# owc-transmitter-ir-v2.net
KiCad netlist of a schematic drawn in EAGLE
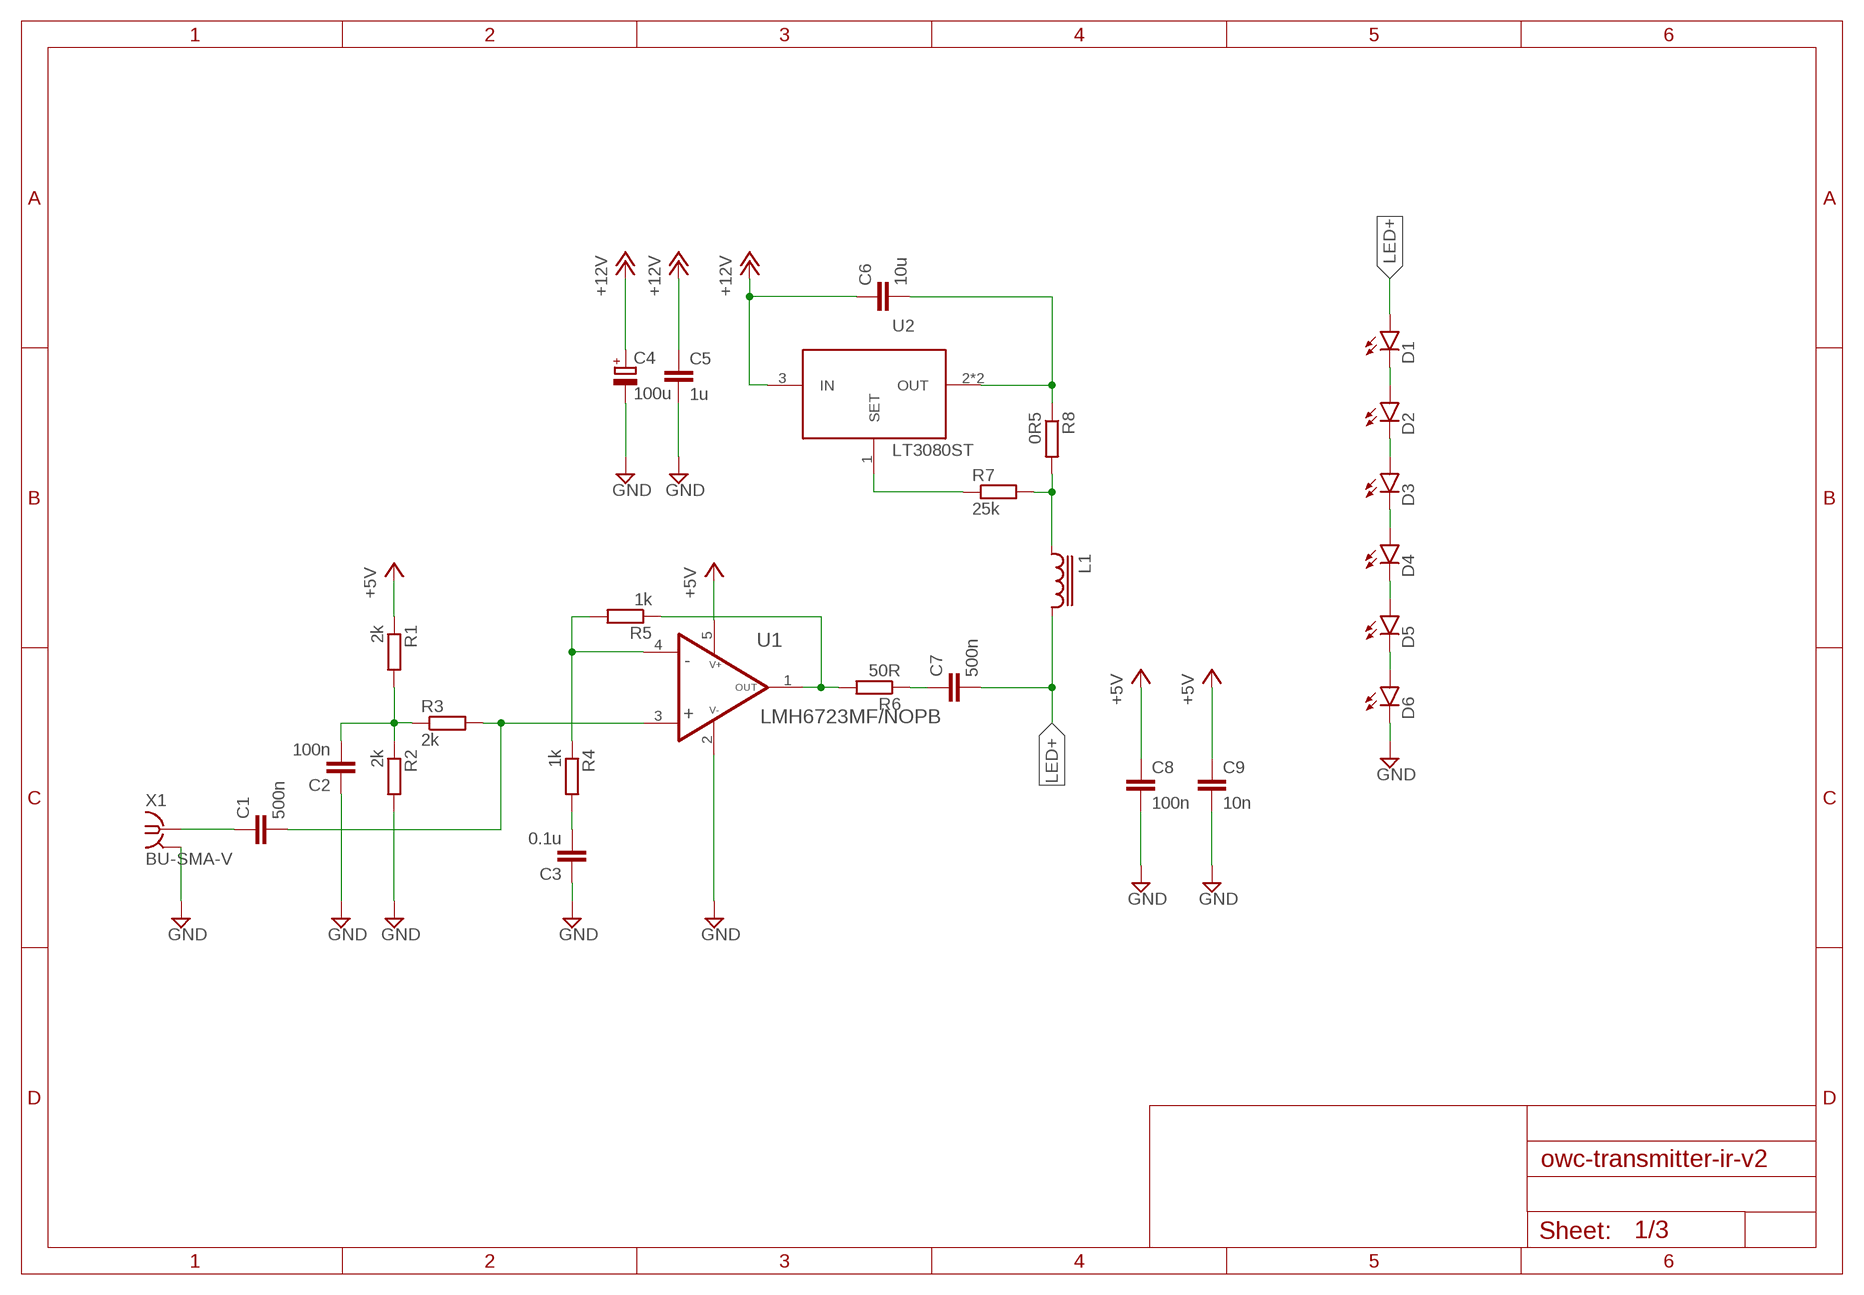
[diagram p0: schematic, sheet 1]
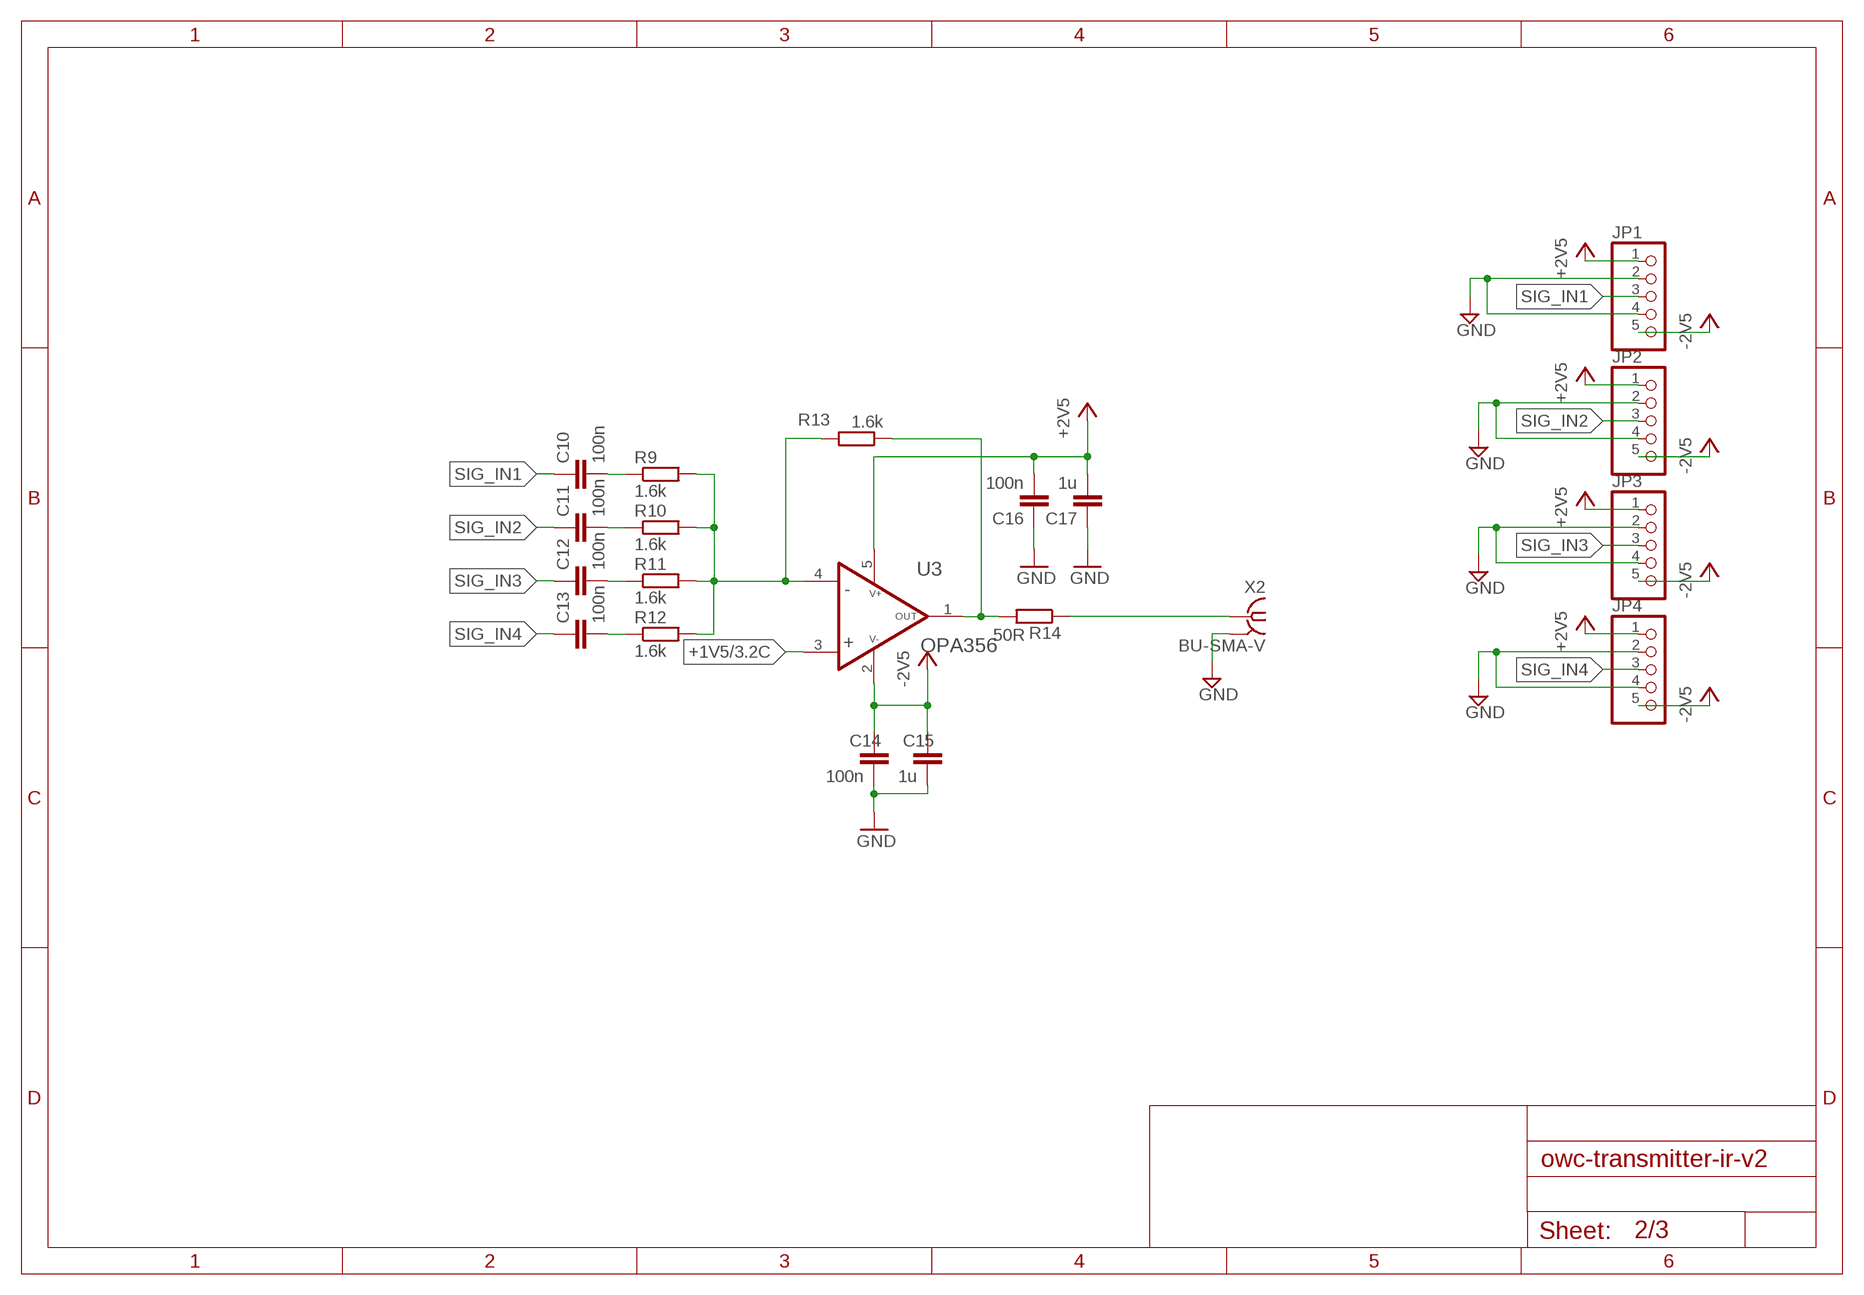
[diagram p1: schematic, sheet 2]
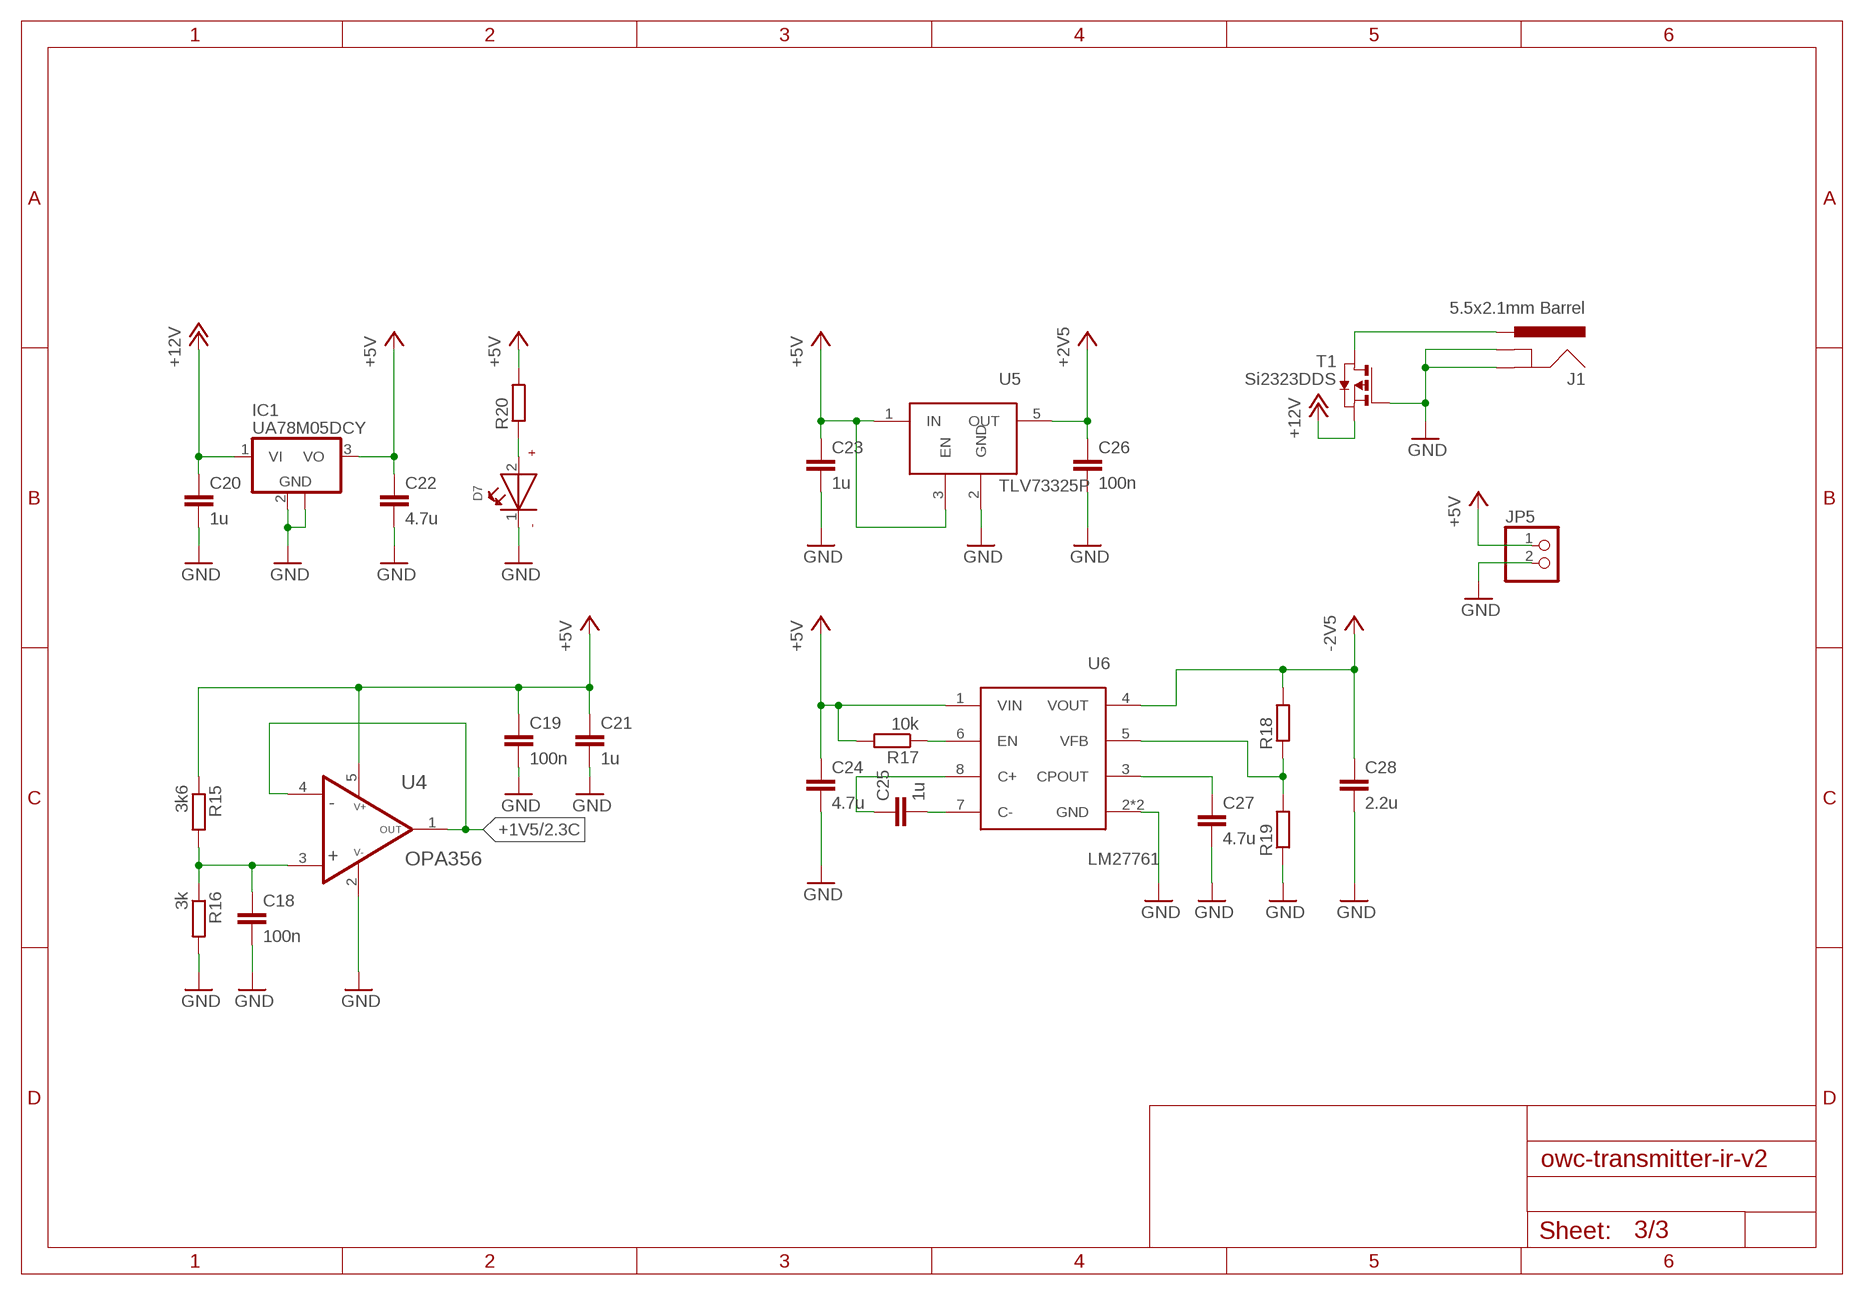
[diagram p2: schematic, sheet 3]

(export (version "E")
  (design (tool "Eeschema 10.0.6"))
  (components
    (comp (ref "C10")
      (value "100n")
      (footprint "eagle-import:C0805")
      (libsource (lib "eagle-import") (part "C-EUC0805"))
    )
    (comp (ref "C11")
      (value "100n")
      (footprint "eagle-import:C0805")
      (libsource (lib "eagle-import") (part "C-EUC0805"))
    )
    (comp (ref "C12")
      (value "100n")
      (footprint "eagle-import:C0805")
      (libsource (lib "eagle-import") (part "C-EUC0805"))
    )
    (comp (ref "C13")
      (value "100n")
      (footprint "eagle-import:C0805")
      (libsource (lib "eagle-import") (part "C-EUC0805"))
    )
    (comp (ref "C14")
      (value "100n")
      (footprint "eagle-import:C0805")
      (libsource (lib "eagle-import") (part "C-EUC0805"))
    )
    (comp (ref "C15")
      (value "1u")
      (footprint "eagle-import:C0805")
      (libsource (lib "eagle-import") (part "C-EUC0805"))
    )
    (comp (ref "C16")
      (value "100n")
      (footprint "eagle-import:C0805")
      (libsource (lib "eagle-import") (part "C-EUC0805"))
    )
    (comp (ref "C17")
      (value "1u")
      (footprint "eagle-import:C0805")
      (libsource (lib "eagle-import") (part "C-EUC0805"))
    )
    (comp (ref "JP1")
      (value "PINHD-1X5")
      (footprint "eagle-import:1X05")
      (libsource (lib "eagle-import") (part "PINHD-1X5"))
    )
    (comp (ref "JP2")
      (value "PINHD-1X5")
      (footprint "eagle-import:1X05")
      (libsource (lib "eagle-import") (part "PINHD-1X5"))
    )
    (comp (ref "JP3")
      (value "PINHD-1X5")
      (footprint "eagle-import:1X05")
      (libsource (lib "eagle-import") (part "PINHD-1X5"))
    )
    (comp (ref "JP4")
      (value "PINHD-1X5")
      (footprint "eagle-import:1X05")
      (libsource (lib "eagle-import") (part "PINHD-1X5"))
    )
    (comp (ref "R9")
      (value "1.6k")
      (footprint "eagle-import:R0805")
      (libsource (lib "eagle-import") (part "R-EU_R0805"))
    )
    (comp (ref "R10")
      (value "1.6k")
      (footprint "eagle-import:R0805")
      (libsource (lib "eagle-import") (part "R-EU_R0805"))
    )
    (comp (ref "R11")
      (value "1.6k")
      (footprint "eagle-import:R0805")
      (libsource (lib "eagle-import") (part "R-EU_R0805"))
    )
    (comp (ref "R12")
      (value "1.6k")
      (footprint "eagle-import:R0805")
      (libsource (lib "eagle-import") (part "R-EU_R0805"))
    )
    (comp (ref "R13")
      (value "1.6k")
      (footprint "eagle-import:R0805")
      (libsource (lib "eagle-import") (part "R-EU_R0805"))
    )
    (comp (ref "R14")
      (value "50R")
      (footprint "eagle-import:R0805")
      (libsource (lib "eagle-import") (part "R-EU_R0805"))
    )
    (comp (ref "U3")
      (value "OPA356")
      (footprint "eagle-import:SOT23-5L")
      (libsource (lib "eagle-import") (part "LMH6629MF"))
    )
    (comp (ref "X2")
      (value "BU-SMA-V")
      (footprint "eagle-import:BU-SMA-V")
      (libsource (lib "eagle-import") (part "BU-SMA-V"))
    )
    (comp (ref "C1")
      (value "500n")
      (footprint "eagle-import:C0805")
      (libsource (lib "eagle-import") (part "C-EUC0805"))
    )
    (comp (ref "C2")
      (value "100n")
      (footprint "eagle-import:C0805")
      (libsource (lib "eagle-import") (part "C-EUC0805"))
    )
    (comp (ref "C3")
      (value "0.1u")
      (footprint "eagle-import:C0805")
      (libsource (lib "eagle-import") (part "C-EUC0805"))
    )
    (comp (ref "C4")
      (value "100u")
      (footprint "eagle-import:CT3528")
      (libsource (lib "eagle-import") (part "CPOL-EUCT3528"))
    )
    (comp (ref "C5")
      (value "1u")
      (footprint "eagle-import:C0805")
      (libsource (lib "eagle-import") (part "C-EUC0805"))
    )
    (comp (ref "C6")
      (value "10u")
      (footprint "eagle-import:C0805")
      (libsource (lib "eagle-import") (part "C-EUC0805"))
    )
    (comp (ref "C7")
      (value "500n")
      (footprint "eagle-import:C0805")
      (libsource (lib "eagle-import") (part "C-EUC0805"))
    )
    (comp (ref "C8")
      (value "100n")
      (footprint "eagle-import:C0805")
      (libsource (lib "eagle-import") (part "C-EUC0805"))
    )
    (comp (ref "C9")
      (value "10n")
      (footprint "eagle-import:C0805")
      (libsource (lib "eagle-import") (part "C-EUC0805"))
    )
    (comp (ref "D1")
      (value "LED5MM")
      (footprint "eagle-import:LED5MM")
      (libsource (lib "eagle-import") (part "LED5MM"))
    )
    (comp (ref "D2")
      (value "LED5MM")
      (footprint "eagle-import:LED5MM")
      (libsource (lib "eagle-import") (part "LED5MM"))
    )
    (comp (ref "D3")
      (value "LED5MM")
      (footprint "eagle-import:LED5MM")
      (libsource (lib "eagle-import") (part "LED5MM"))
    )
    (comp (ref "D4")
      (value "LED5MM")
      (footprint "eagle-import:LED5MM")
      (libsource (lib "eagle-import") (part "LED5MM"))
    )
    (comp (ref "D5")
      (value "LED5MM")
      (footprint "eagle-import:LED5MM")
      (libsource (lib "eagle-import") (part "LED5MM"))
    )
    (comp (ref "D6")
      (value "LED5MM")
      (footprint "eagle-import:LED5MM")
      (libsource (lib "eagle-import") (part "LED5MM"))
    )
    (comp (ref "L1")
      (value "SRR6603")
      (footprint "eagle-import:SRR6603")
      (libsource (lib "eagle-import") (part "SRR6603"))
    )
    (comp (ref "R1")
      (value "2k")
      (footprint "eagle-import:R0805")
      (libsource (lib "eagle-import") (part "R-EU_R0805"))
    )
    (comp (ref "R2")
      (value "2k")
      (footprint "eagle-import:R0805")
      (libsource (lib "eagle-import") (part "R-EU_R0805"))
    )
    (comp (ref "R3")
      (value "2k")
      (footprint "eagle-import:R0805")
      (libsource (lib "eagle-import") (part "R-EU_R0805"))
    )
    (comp (ref "R4")
      (value "1k")
      (footprint "eagle-import:R0805")
      (libsource (lib "eagle-import") (part "R-EU_R0805"))
    )
    (comp (ref "R5")
      (value "1k")
      (footprint "eagle-import:R0805")
      (libsource (lib "eagle-import") (part "R-EU_R0805"))
    )
    (comp (ref "R6")
      (value "50R")
      (footprint "eagle-import:R0805")
      (libsource (lib "eagle-import") (part "R-EU_R0805"))
    )
    (comp (ref "R7")
      (value "25k")
      (footprint "eagle-import:R0805")
      (libsource (lib "eagle-import") (part "R-EU_R0805"))
    )
    (comp (ref "R8")
      (value "0R5")
      (footprint "eagle-import:R0805")
      (libsource (lib "eagle-import") (part "R-EU_R0805"))
    )
    (comp (ref "U1")
      (value "LMH6723MF/NOPB")
      (footprint "eagle-import:SOT23-5L")
      (libsource (lib "eagle-import") (part "LMH6723MF/NOPB"))
    )
    (comp (ref "U2")
      (value "LT3080ST")
      (footprint "eagle-import:SOT223")
      (libsource (lib "eagle-import") (part "LT3080ST"))
    )
    (comp (ref "X1")
      (value "BU-SMA-V")
      (footprint "eagle-import:BU-SMA-V")
      (libsource (lib "eagle-import") (part "BU-SMA-V"))
    )
    (comp (ref "C18")
      (value "100n")
      (footprint "eagle-import:C0805")
      (libsource (lib "eagle-import") (part "C-EUC0805"))
    )
    (comp (ref "C19")
      (value "100n")
      (footprint "eagle-import:C0805")
      (libsource (lib "eagle-import") (part "C-EUC0805"))
    )
    (comp (ref "C20")
      (value "1u")
      (footprint "eagle-import:C0805")
      (libsource (lib "eagle-import") (part "C-EUC0805"))
    )
    (comp (ref "C21")
      (value "1u")
      (footprint "eagle-import:C0805")
      (libsource (lib "eagle-import") (part "C-EUC0805"))
    )
    (comp (ref "C22")
      (value "4.7u")
      (footprint "eagle-import:C0805")
      (libsource (lib "eagle-import") (part "C-EUC0805"))
    )
    (comp (ref "C23")
      (value "1u")
      (footprint "eagle-import:C0805")
      (libsource (lib "eagle-import") (part "C-EUC0805"))
    )
    (comp (ref "C24")
      (value "4.7u")
      (footprint "eagle-import:C0805")
      (libsource (lib "eagle-import") (part "C-EUC0805"))
    )
    (comp (ref "C25")
      (value "1u")
      (footprint "eagle-import:C0805")
      (libsource (lib "eagle-import") (part "C-EUC0805"))
    )
    (comp (ref "C26")
      (value "100n")
      (footprint "eagle-import:C0805")
      (libsource (lib "eagle-import") (part "C-EUC0805"))
    )
    (comp (ref "C27")
      (value "4.7u")
      (footprint "eagle-import:C0805")
      (libsource (lib "eagle-import") (part "C-EUC0805"))
    )
    (comp (ref "C28")
      (value "2.2u")
      (footprint "eagle-import:C0805")
      (libsource (lib "eagle-import") (part "C-EUC0805"))
    )
    (comp (ref "D7")
      (value "WL-SMCW-150080GS75000-G")
      (footprint "eagle-import:WL-SMCW_0805")
      (libsource (lib "eagle-import") (part "WL-SMCW-150080GS75000-G"))
    )
    (comp (ref "IC1")
      (value "UA78M05DCY")
      (footprint "eagle-import:SOT223")
      (libsource (lib "eagle-import") (part "UA78MDCY05"))
    )
    (comp (ref "J1")
      (value "5.5x2.1mm Barrel")
      (footprint "eagle-import:POWER_JACK_SMD")
      (libsource (lib "eagle-import") (part "POWER_JACKSMD"))
    )
    (comp (ref "JP5")
      (value "PINHD-1X2")
      (footprint "eagle-import:1X02")
      (libsource (lib "eagle-import") (part "PINHD-1X2"))
    )
    (comp (ref "R15")
      (value "3k6")
      (footprint "eagle-import:R0805")
      (libsource (lib "eagle-import") (part "R-EU_R0805"))
    )
    (comp (ref "R16")
      (value "3k")
      (footprint "eagle-import:R0805")
      (libsource (lib "eagle-import") (part "R-EU_R0805"))
    )
    (comp (ref "R17")
      (value "10k")
      (footprint "eagle-import:R0805")
      (libsource (lib "eagle-import") (part "R-EU_R0805"))
    )
    (comp (ref "R18")
      (value "R-EU_R0805")
      (footprint "eagle-import:R0805")
      (libsource (lib "eagle-import") (part "R-EU_R0805"))
    )
    (comp (ref "R19")
      (value "R-EU_R0805")
      (footprint "eagle-import:R0805")
      (libsource (lib "eagle-import") (part "R-EU_R0805"))
    )
    (comp (ref "R20")
      (value "R-EU_R0805")
      (footprint "eagle-import:R0805")
      (libsource (lib "eagle-import") (part "R-EU_R0805"))
    )
    (comp (ref "T1")
      (value "Si2323DDS")
      (footprint "eagle-import:SOT-23")
      (libsource (lib "eagle-import") (part "PMOSSOT23"))
    )
    (comp (ref "U4")
      (value "OPA356")
      (footprint "eagle-import:SOT23-5L")
      (libsource (lib "eagle-import") (part "LMH6629MF"))
    )
    (comp (ref "U5")
      (value "TLV73325P")
      (footprint "eagle-import:SOT23-5L")
      (libsource (lib "eagle-import") (part "V_REG5-FIXEDEN"))
    )
    (comp (ref "U6")
      (value "LM27761DSG")
      (footprint "eagle-import:WSON-8-PAD")
      (fields (field (name "MPN") "LM27761DSGT"))
      (libsource (lib "eagle-import") (part "LM27761DSG"))
    )
  )
  (nets
    (net (code "1") (name "+1V5") (class "Default")
      (node (ref "U3") (pin "3") (pinfunction "IN+_3") (pintype "input"))
      (node (ref "U4") (pin "1") (pinfunction "OUT_1") (pintype "output"))
      (node (ref "U4") (pin "4") (pinfunction "IN-_4") (pintype "input"))
    )
    (net (code "2") (name "+2V5") (class "Default")
      (node (ref "C16") (pin "2") (pinfunction "2_2") (pintype "passive"))
      (node (ref "C17") (pin "2") (pinfunction "2_2") (pintype "passive"))
      (node (ref "C26") (pin "1") (pinfunction "1_1") (pintype "passive"))
      (node (ref "JP1") (pin "1") (pinfunction "1_1") (pintype "passive"))
      (node (ref "JP2") (pin "1") (pinfunction "1_1") (pintype "passive"))
      (node (ref "JP3") (pin "1") (pinfunction "1_1") (pintype "passive"))
      (node (ref "JP4") (pin "1") (pinfunction "1_1") (pintype "passive"))
      (node (ref "U3") (pin "5") (pinfunction "V+_5") (pintype "power_in"))
      (node (ref "U5") (pin "5") (pinfunction "OUT_5") (pintype "passive"))
    )
    (net (code "3") (name "+5V") (class "Default")
      (node (ref "C19") (pin "1") (pinfunction "1_1") (pintype "passive"))
      (node (ref "C21") (pin "1") (pinfunction "1_1") (pintype "passive"))
      (node (ref "C22") (pin "1") (pinfunction "1_1") (pintype "passive"))
      (node (ref "C23") (pin "1") (pinfunction "1_1") (pintype "passive"))
      (node (ref "C24") (pin "1") (pinfunction "1_1") (pintype "passive"))
      (node (ref "C8") (pin "1") (pinfunction "1_1") (pintype "passive"))
      (node (ref "C9") (pin "1") (pinfunction "1_1") (pintype "passive"))
      (node (ref "IC1") (pin "3") (pinfunction "VO_3") (pintype "passive"))
      (node (ref "JP5") (pin "1") (pinfunction "1_1") (pintype "passive"))
      (node (ref "R1") (pin "1") (pinfunction "1_1") (pintype "passive"))
      (node (ref "R15") (pin "1") (pinfunction "1_1") (pintype "passive"))
      (node (ref "R17") (pin "2") (pinfunction "2_2") (pintype "passive"))
      (node (ref "R20") (pin "2") (pinfunction "2_2") (pintype "passive"))
      (node (ref "U1") (pin "5") (pinfunction "V+_5") (pintype "power_in"))
      (node (ref "U4") (pin "5") (pinfunction "V+_5") (pintype "power_in"))
      (node (ref "U5") (pin "1") (pinfunction "IN_1") (pintype "power_in"))
      (node (ref "U5") (pin "3") (pinfunction "EN_3") (pintype "bidirectional"))
      (node (ref "U6") (pin "1") (pinfunction "VIN_1") (pintype "bidirectional"))
    )
    (net (code "4") (name "+12V") (class "Default")
      (node (ref "C20") (pin "1") (pinfunction "1_1") (pintype "passive"))
      (node (ref "C4") (pin "+") (pinfunction "+_+") (pintype "passive"))
      (node (ref "C5") (pin "1") (pinfunction "1_1") (pintype "passive"))
      (node (ref "C6") (pin "1") (pinfunction "1_1") (pintype "passive"))
      (node (ref "IC1") (pin "1") (pinfunction "VI_1") (pintype "input"))
      (node (ref "T1") (pin "2") (pinfunction "S_2") (pintype "passive"))
      (node (ref "U2") (pin "3") (pinfunction "IN_3") (pintype "power_in"))
    )
    (net (code "5") (name "-2V5") (class "Default")
      (node (ref "C14") (pin "1") (pinfunction "1_1") (pintype "passive"))
      (node (ref "C15") (pin "1") (pinfunction "1_1") (pintype "passive"))
      (node (ref "C28") (pin "1") (pinfunction "1_1") (pintype "passive"))
      (node (ref "JP1") (pin "5") (pinfunction "5_5") (pintype "passive"))
      (node (ref "JP2") (pin "5") (pinfunction "5_5") (pintype "passive"))
      (node (ref "JP3") (pin "5") (pinfunction "5_5") (pintype "passive"))
      (node (ref "JP4") (pin "5") (pinfunction "5_5") (pintype "passive"))
      (node (ref "R18") (pin "2") (pinfunction "2_2") (pintype "passive"))
      (node (ref "U3") (pin "2") (pinfunction "V-_2") (pintype "power_in"))
      (node (ref "U6") (pin "4") (pinfunction "VOUT_4") (pintype "bidirectional"))
    )
    (net (code "6") (name "GND") (class "Default")
      (node (ref "C14") (pin "2") (pinfunction "2_2") (pintype "passive"))
      (node (ref "C15") (pin "2") (pinfunction "2_2") (pintype "passive"))
      (node (ref "C16") (pin "1") (pinfunction "1_1") (pintype "passive"))
      (node (ref "C17") (pin "1") (pinfunction "1_1") (pintype "passive"))
      (node (ref "C18") (pin "2") (pinfunction "2_2") (pintype "passive"))
      (node (ref "C19") (pin "2") (pinfunction "2_2") (pintype "passive"))
      (node (ref "C2") (pin "1") (pinfunction "1_1") (pintype "passive"))
      (node (ref "C20") (pin "2") (pinfunction "2_2") (pintype "passive"))
      (node (ref "C21") (pin "2") (pinfunction "2_2") (pintype "passive"))
      (node (ref "C22") (pin "2") (pinfunction "2_2") (pintype "passive"))
      (node (ref "C23") (pin "2") (pinfunction "2_2") (pintype "passive"))
      (node (ref "C24") (pin "2") (pinfunction "2_2") (pintype "passive"))
      (node (ref "C26") (pin "2") (pinfunction "2_2") (pintype "passive"))
      (node (ref "C27") (pin "2") (pinfunction "2_2") (pintype "passive"))
      (node (ref "C28") (pin "2") (pinfunction "2_2") (pintype "passive"))
      (node (ref "C3") (pin "1") (pinfunction "1_1") (pintype "passive"))
      (node (ref "C4") (pin "-") (pinfunction "-_-") (pintype "passive"))
      (node (ref "C5") (pin "2") (pinfunction "2_2") (pintype "passive"))
      (node (ref "C8") (pin "2") (pinfunction "2_2") (pintype "passive"))
      (node (ref "C9") (pin "2") (pinfunction "2_2") (pintype "passive"))
      (node (ref "D6") (pin "K") (pinfunction "C_K") (pintype "passive"))
      (node (ref "D7") (pin "1") (pinfunction "-_1") (pintype "passive"))
      (node (ref "IC1") (pin "2") (pinfunction "GND_2") (pintype "passive"))
      (node (ref "IC1") (pin "4") (pinfunction "GND_4") (pintype "passive"))
      (node (ref "J1") (pin "GND") (pinfunction "GNDBREAK_GND") (pintype "bidirectional"))
      (node (ref "J1") (pin "P$4") (pinfunction "GND_P$4") (pintype "bidirectional"))
      (node (ref "JP1") (pin "2") (pinfunction "2_2") (pintype "passive"))
      (node (ref "JP1") (pin "4") (pinfunction "4_4") (pintype "passive"))
      (node (ref "JP2") (pin "2") (pinfunction "2_2") (pintype "passive"))
      (node (ref "JP2") (pin "4") (pinfunction "4_4") (pintype "passive"))
      (node (ref "JP3") (pin "2") (pinfunction "2_2") (pintype "passive"))
      (node (ref "JP3") (pin "4") (pinfunction "4_4") (pintype "passive"))
      (node (ref "JP4") (pin "2") (pinfunction "2_2") (pintype "passive"))
      (node (ref "JP4") (pin "4") (pinfunction "4_4") (pintype "passive"))
      (node (ref "JP5") (pin "2") (pinfunction "2_2") (pintype "passive"))
      (node (ref "R16") (pin "2") (pinfunction "2_2") (pintype "passive"))
      (node (ref "R19") (pin "1") (pinfunction "1_1") (pintype "passive"))
      (node (ref "R2") (pin "2") (pinfunction "2_2") (pintype "passive"))
      (node (ref "T1") (pin "3") (pinfunction "G_3") (pintype "passive"))
      (node (ref "U1") (pin "2") (pinfunction "V-_2") (pintype "power_in"))
      (node (ref "U4") (pin "2") (pinfunction "V-_2") (pintype "power_in"))
      (node (ref "U5") (pin "2") (pinfunction "GND_2") (pintype "passive"))
      (node (ref "U6") (pin "2") (pinfunction "GND_2") (pintype "bidirectional"))
      (node (ref "U6") (pin "PAD") (pinfunction "GND_PAD") (pintype "bidirectional"))
      (node (ref "X1") (pin "2") (pinfunction "2_2") (pintype "passive"))
      (node (ref "X1") (pin "3") (pinfunction "2_3") (pintype "passive"))
      (node (ref "X1") (pin "4") (pinfunction "2_4") (pintype "passive"))
      (node (ref "X1") (pin "5") (pinfunction "2_5") (pintype "passive"))
      (node (ref "X2") (pin "2") (pinfunction "2_2") (pintype "passive"))
      (node (ref "X2") (pin "3") (pinfunction "2_3") (pintype "passive"))
      (node (ref "X2") (pin "4") (pinfunction "2_4") (pintype "passive"))
      (node (ref "X2") (pin "5") (pinfunction "2_5") (pintype "passive"))
    )
    (net (code "7") (name "LED+") (class "Default")
      (node (ref "C7") (pin "2") (pinfunction "2_2") (pintype "passive"))
      (node (ref "D1") (pin "A") (pinfunction "A_A") (pintype "passive"))
      (node (ref "L1") (pin "P$2") (pinfunction "2_P$2") (pintype "passive"))
    )
    (net (code "8") (name "Net-(C1-Pad1)") (class "Default")
      (node (ref "C1") (pin "1") (pinfunction "1_1") (pintype "passive"))
      (node (ref "X1") (pin "1") (pinfunction "1_1") (pintype "passive"))
    )
    (net (code "9") (name "Net-(C2-Pad2)") (class "Default")
      (node (ref "C2") (pin "2") (pinfunction "2_2") (pintype "passive"))
      (node (ref "R1") (pin "2") (pinfunction "2_2") (pintype "passive"))
      (node (ref "R2") (pin "1") (pinfunction "1_1") (pintype "passive"))
      (node (ref "R3") (pin "1") (pinfunction "1_1") (pintype "passive"))
    )
    (net (code "10") (name "Net-(C3-Pad2)") (class "Default")
      (node (ref "C3") (pin "2") (pinfunction "2_2") (pintype "passive"))
      (node (ref "R4") (pin "2") (pinfunction "2_2") (pintype "passive"))
    )
    (net (code "11") (name "Net-(C6-Pad2)") (class "Default")
      (node (ref "C6") (pin "2") (pinfunction "2_2") (pintype "passive"))
      (node (ref "R8") (pin "1") (pinfunction "1_1") (pintype "passive"))
      (node (ref "U2") (pin "2") (pinfunction "OUT_2") (pintype "passive"))
      (node (ref "U2") (pin "4") (pinfunction "OUT_4") (pintype "passive"))
    )
    (net (code "12") (name "Net-(C7-Pad1)") (class "Default")
      (node (ref "C7") (pin "1") (pinfunction "1_1") (pintype "passive"))
      (node (ref "R6") (pin "1") (pinfunction "1_1") (pintype "passive"))
    )
    (net (code "13") (name "Net-(C10-Pad2)") (class "Default")
      (node (ref "C10") (pin "2") (pinfunction "2_2") (pintype "passive"))
      (node (ref "R9") (pin "1") (pinfunction "1_1") (pintype "passive"))
    )
    (net (code "14") (name "Net-(C11-Pad2)") (class "Default")
      (node (ref "C11") (pin "2") (pinfunction "2_2") (pintype "passive"))
      (node (ref "R10") (pin "1") (pinfunction "1_1") (pintype "passive"))
    )
    (net (code "15") (name "Net-(C12-Pad2)") (class "Default")
      (node (ref "C12") (pin "2") (pinfunction "2_2") (pintype "passive"))
      (node (ref "R11") (pin "1") (pinfunction "1_1") (pintype "passive"))
    )
    (net (code "16") (name "Net-(C13-Pad2)") (class "Default")
      (node (ref "C13") (pin "2") (pinfunction "2_2") (pintype "passive"))
      (node (ref "R12") (pin "1") (pinfunction "1_1") (pintype "passive"))
    )
    (net (code "17") (name "Net-(D1-C)") (class "Default")
      (node (ref "D1") (pin "K") (pinfunction "C_K") (pintype "passive"))
      (node (ref "D2") (pin "A") (pinfunction "A_A") (pintype "passive"))
    )
    (net (code "18") (name "Net-(D2-C)") (class "Default")
      (node (ref "D2") (pin "K") (pinfunction "C_K") (pintype "passive"))
      (node (ref "D3") (pin "A") (pinfunction "A_A") (pintype "passive"))
    )
    (net (code "19") (name "Net-(D3-C)") (class "Default")
      (node (ref "D3") (pin "K") (pinfunction "C_K") (pintype "passive"))
      (node (ref "D4") (pin "A") (pinfunction "A_A") (pintype "passive"))
    )
    (net (code "20") (name "Net-(D4-C)") (class "Default")
      (node (ref "D4") (pin "K") (pinfunction "C_K") (pintype "passive"))
      (node (ref "D5") (pin "A") (pinfunction "A_A") (pintype "passive"))
    )
    (net (code "21") (name "Net-(D5-C)") (class "Default")
      (node (ref "D5") (pin "K") (pinfunction "C_K") (pintype "passive"))
      (node (ref "D6") (pin "A") (pinfunction "A_A") (pintype "passive"))
    )
    (net (code "22") (name "Net-(D7-+)") (class "Default")
      (node (ref "D7") (pin "2") (pinfunction "+_2") (pintype "passive"))
      (node (ref "R20") (pin "1") (pinfunction "1_1") (pintype "passive"))
    )
    (net (code "23") (name "Net-(J1-PWR)") (class "Default")
      (node (ref "J1") (pin "VIN0") (pinfunction "PWR_VIN0") (pintype "bidirectional"))
      (node (ref "T1") (pin "1") (pinfunction "D_1") (pintype "passive"))
    )
    (net (code "24") (name "Net-(L1-1)") (class "Default")
      (node (ref "L1") (pin "P$1") (pinfunction "1_P$1") (pintype "passive"))
      (node (ref "R7") (pin "2") (pinfunction "2_2") (pintype "passive"))
      (node (ref "R8") (pin "2") (pinfunction "2_2") (pintype "passive"))
    )
    (net (code "25") (name "Net-(R14-Pad1)") (class "Default")
      (node (ref "R14") (pin "1") (pinfunction "1_1") (pintype "passive"))
      (node (ref "X2") (pin "1") (pinfunction "1_1") (pintype "passive"))
    )
    (net (code "26") (name "Net-(U1-IN+)") (class "Default")
      (node (ref "C1") (pin "2") (pinfunction "2_2") (pintype "passive"))
      (node (ref "R3") (pin "2") (pinfunction "2_2") (pintype "passive"))
      (node (ref "U1") (pin "3") (pinfunction "IN+_3") (pintype "input"))
    )
    (net (code "27") (name "Net-(U1-IN-)") (class "Default")
      (node (ref "R4") (pin "1") (pinfunction "1_1") (pintype "passive"))
      (node (ref "R5") (pin "2") (pinfunction "2_2") (pintype "passive"))
      (node (ref "U1") (pin "4") (pinfunction "IN-_4") (pintype "input"))
    )
    (net (code "28") (name "Net-(U1-OUT)") (class "Default")
      (node (ref "R5") (pin "1") (pinfunction "1_1") (pintype "passive"))
      (node (ref "R6") (pin "2") (pinfunction "2_2") (pintype "passive"))
      (node (ref "U1") (pin "1") (pinfunction "OUT_1") (pintype "output"))
    )
    (net (code "29") (name "Net-(U2-SET)") (class "Default")
      (node (ref "R7") (pin "1") (pinfunction "1_1") (pintype "passive"))
      (node (ref "U2") (pin "1") (pinfunction "SET_1") (pintype "passive"))
    )
    (net (code "30") (name "Net-(U3-IN-)") (class "Default")
      (node (ref "R10") (pin "2") (pinfunction "2_2") (pintype "passive"))
      (node (ref "R11") (pin "2") (pinfunction "2_2") (pintype "passive"))
      (node (ref "R12") (pin "2") (pinfunction "2_2") (pintype "passive"))
      (node (ref "R13") (pin "2") (pinfunction "2_2") (pintype "passive"))
      (node (ref "R9") (pin "2") (pinfunction "2_2") (pintype "passive"))
      (node (ref "U3") (pin "4") (pinfunction "IN-_4") (pintype "input"))
    )
    (net (code "31") (name "Net-(U3-OUT)") (class "Default")
      (node (ref "R13") (pin "1") (pinfunction "1_1") (pintype "passive"))
      (node (ref "R14") (pin "2") (pinfunction "2_2") (pintype "passive"))
      (node (ref "U3") (pin "1") (pinfunction "OUT_1") (pintype "output"))
    )
    (net (code "32") (name "Net-(U4-IN+)") (class "Default")
      (node (ref "C18") (pin "1") (pinfunction "1_1") (pintype "passive"))
      (node (ref "R15") (pin "2") (pinfunction "2_2") (pintype "passive"))
      (node (ref "R16") (pin "1") (pinfunction "1_1") (pintype "passive"))
      (node (ref "U4") (pin "3") (pinfunction "IN+_3") (pintype "input"))
    )
    (net (code "33") (name "Net-(U6-C+)") (class "Default")
      (node (ref "C25") (pin "1") (pinfunction "1_1") (pintype "passive"))
      (node (ref "U6") (pin "8") (pinfunction "C+_8") (pintype "bidirectional"))
    )
    (net (code "34") (name "Net-(U6-C-)") (class "Default")
      (node (ref "C25") (pin "2") (pinfunction "2_2") (pintype "passive"))
      (node (ref "U6") (pin "7") (pinfunction "C-_7") (pintype "bidirectional"))
    )
    (net (code "35") (name "Net-(U6-CPOUT)") (class "Default")
      (node (ref "C27") (pin "1") (pinfunction "1_1") (pintype "passive"))
      (node (ref "U6") (pin "3") (pinfunction "CPOUT_3") (pintype "bidirectional"))
    )
    (net (code "36") (name "Net-(U6-EN)") (class "Default")
      (node (ref "R17") (pin "1") (pinfunction "1_1") (pintype "passive"))
      (node (ref "U6") (pin "6") (pinfunction "EN_6") (pintype "bidirectional"))
    )
    (net (code "37") (name "Net-(U6-VFB)") (class "Default")
      (node (ref "R18") (pin "1") (pinfunction "1_1") (pintype "passive"))
      (node (ref "R19") (pin "2") (pinfunction "2_2") (pintype "passive"))
      (node (ref "U6") (pin "5") (pinfunction "VFB_5") (pintype "bidirectional"))
    )
    (net (code "38") (name "SIG_IN1") (class "Default")
      (node (ref "C10") (pin "1") (pinfunction "1_1") (pintype "passive"))
      (node (ref "JP1") (pin "3") (pinfunction "3_3") (pintype "passive"))
    )
    (net (code "39") (name "SIG_IN2") (class "Default")
      (node (ref "C11") (pin "1") (pinfunction "1_1") (pintype "passive"))
      (node (ref "JP2") (pin "3") (pinfunction "3_3") (pintype "passive"))
    )
    (net (code "40") (name "SIG_IN3") (class "Default")
      (node (ref "C12") (pin "1") (pinfunction "1_1") (pintype "passive"))
      (node (ref "JP3") (pin "3") (pinfunction "3_3") (pintype "passive"))
    )
    (net (code "41") (name "SIG_IN4") (class "Default")
      (node (ref "C13") (pin "1") (pinfunction "1_1") (pintype "passive"))
      (node (ref "JP4") (pin "3") (pinfunction "3_3") (pintype "passive"))
    )
  )
)
